# 08_FPGA_banks_1_2_3_4.net
KiCad netlist of a schematic drawn in Altium Designer
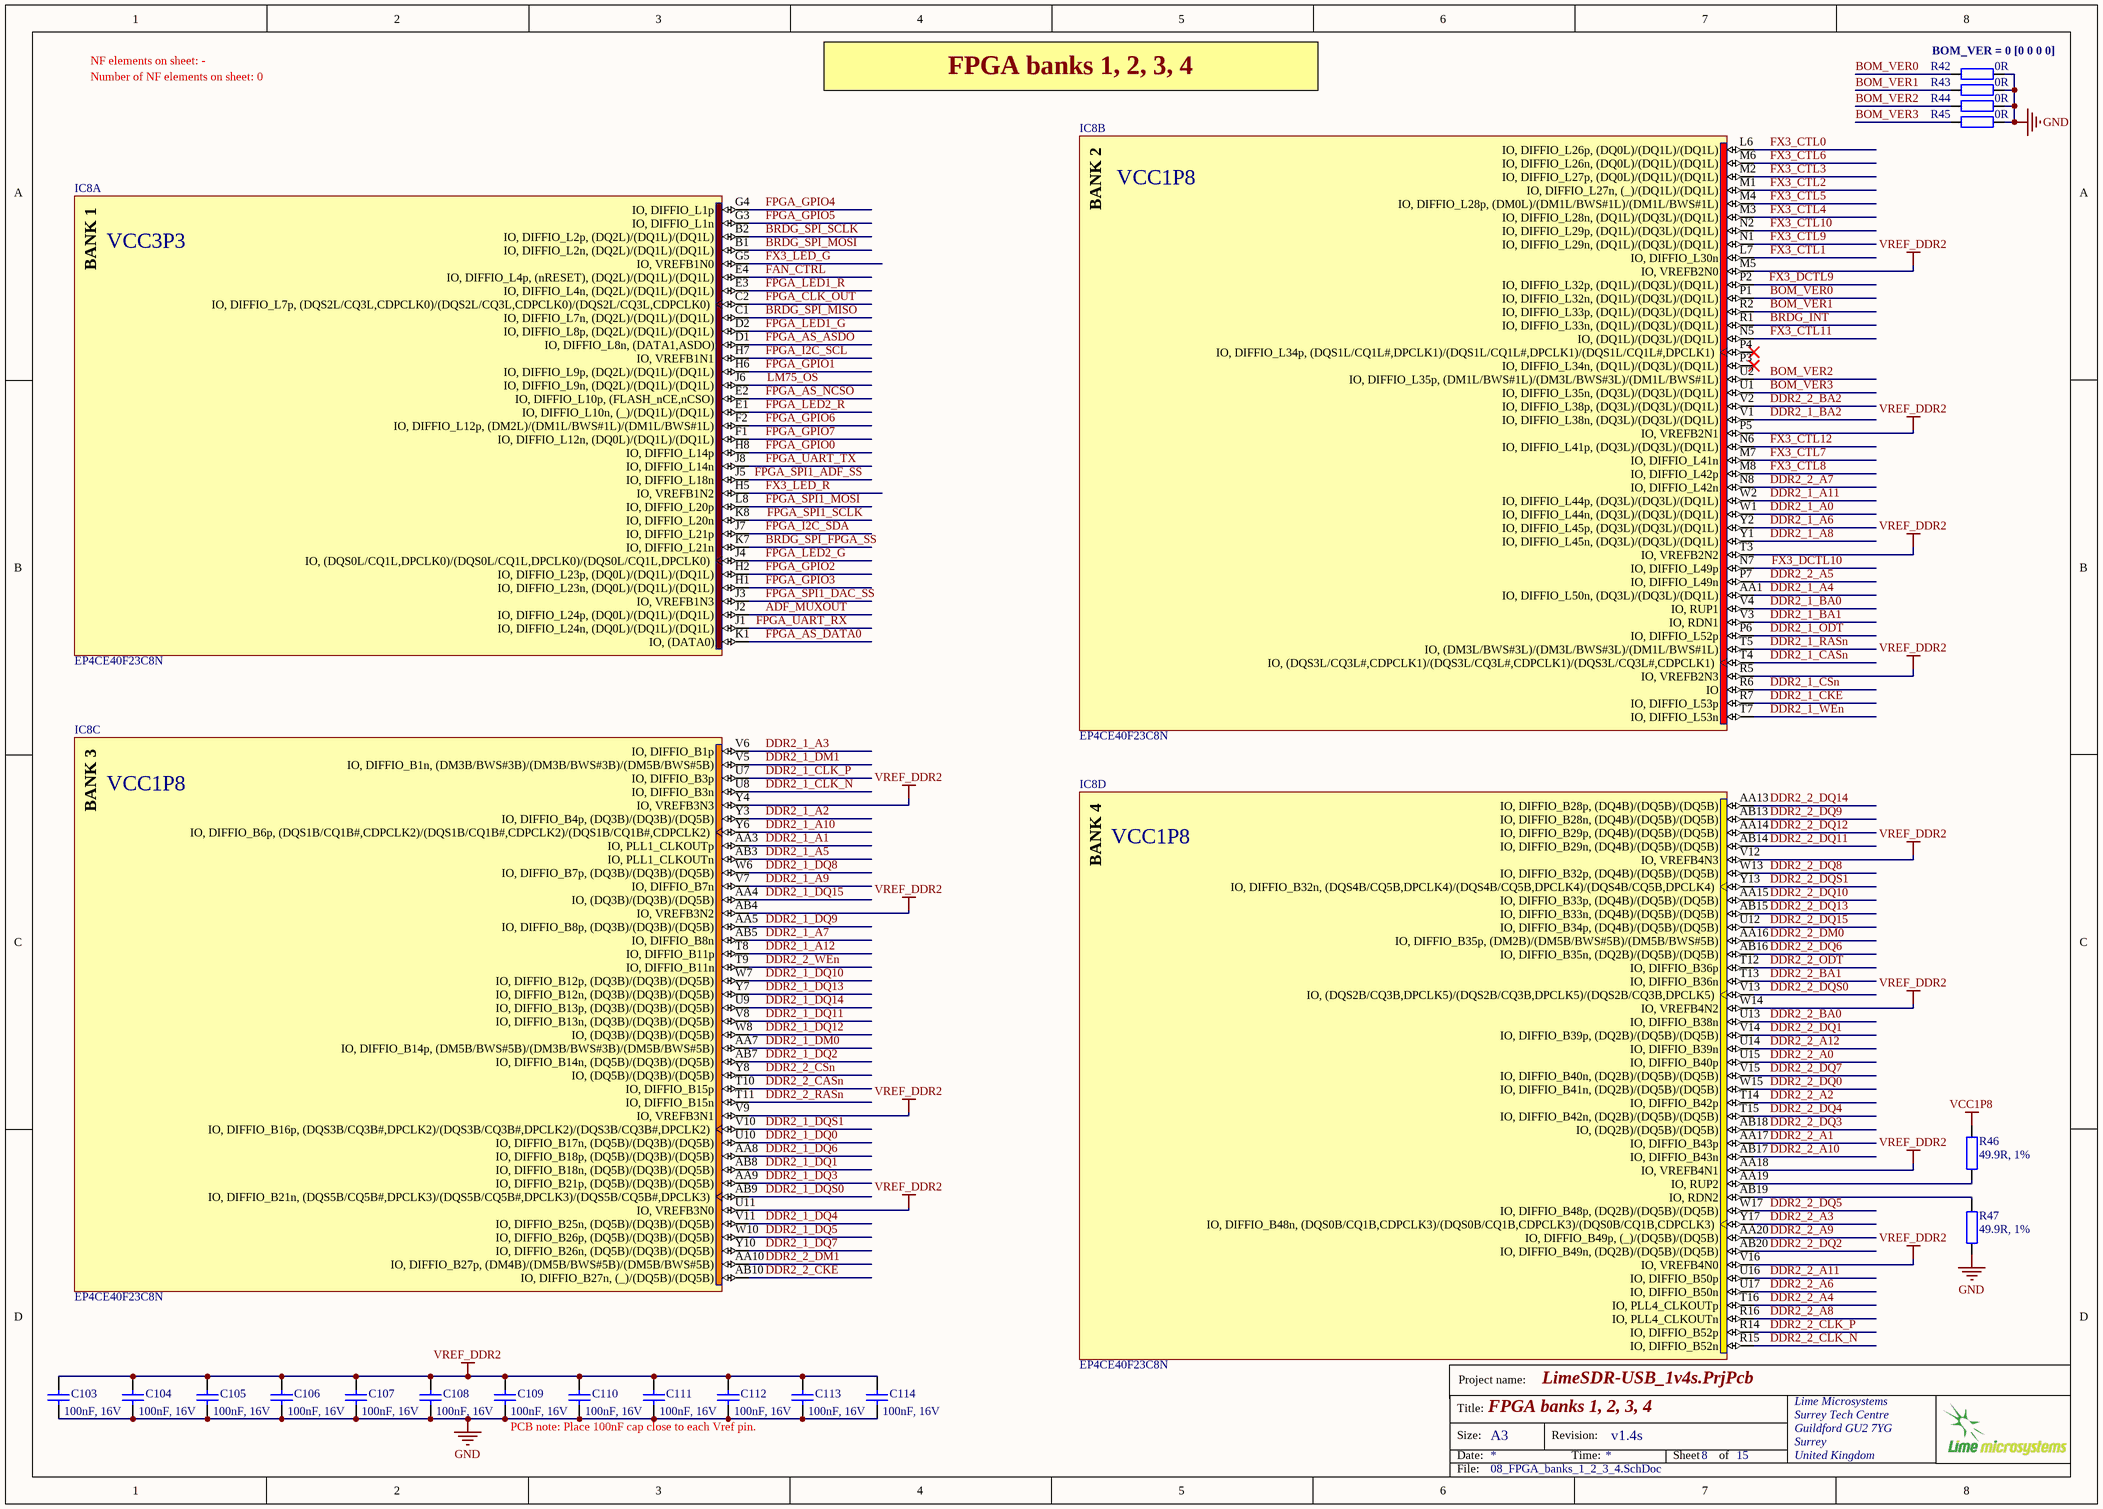
[diagram p0: 08_FPGA_banks_1_2_3_4.SchDoc]

(export (version "E")
  (design (tool "Eeschema 10.0.6"))
  (components
    (comp (ref "C103")
      (value "100nF, 16V")
      (footprint "CAP0402")
      (fields
        (field (name "TOLERANCE") "10 %")
        (field (name "MANUFACTURER") "Murata Electronics")
        (field (name "MANUFACTURER PART NUMBER") "GRM155R71C104KA88D")
      )
      (libsource (lib "LimeFPGAboard_schLib") (part "Cap_0603"))
    )
    (comp (ref "C104")
      (value "100nF, 16V")
      (footprint "CAP0402")
      (fields
        (field (name "TOLERANCE") "10 %")
        (field (name "MANUFACTURER") "Murata Electronics")
        (field (name "MANUFACTURER PART NUMBER") "GRM155R71C104KA88D")
      )
      (libsource (lib "LimeFPGAboard_schLib") (part "Cap_0603"))
    )
    (comp (ref "C105")
      (value "100nF, 16V")
      (footprint "CAP0402")
      (fields
        (field (name "TOLERANCE") "10 %")
        (field (name "MANUFACTURER") "Murata Electronics")
        (field (name "MANUFACTURER PART NUMBER") "GRM155R71C104KA88D")
      )
      (libsource (lib "LimeFPGAboard_schLib") (part "Cap_0603"))
    )
    (comp (ref "C106")
      (value "100nF, 16V")
      (footprint "CAP0402")
      (fields
        (field (name "TOLERANCE") "10 %")
        (field (name "MANUFACTURER") "Murata Electronics")
        (field (name "MANUFACTURER PART NUMBER") "GRM155R71C104KA88D")
      )
      (libsource (lib "LimeFPGAboard_schLib") (part "Cap_0603"))
    )
    (comp (ref "C107")
      (value "100nF, 16V")
      (footprint "CAP0402")
      (fields
        (field (name "TOLERANCE") "10 %")
        (field (name "MANUFACTURER") "Murata Electronics")
        (field (name "MANUFACTURER PART NUMBER") "GRM155R71C104KA88D")
      )
      (libsource (lib "LimeFPGAboard_schLib") (part "Cap_0603"))
    )
    (comp (ref "C108")
      (value "100nF, 16V")
      (footprint "CAP0402")
      (fields
        (field (name "TOLERANCE") "10 %")
        (field (name "MANUFACTURER") "Murata Electronics")
        (field (name "MANUFACTURER PART NUMBER") "GRM155R71C104KA88D")
      )
      (libsource (lib "LimeFPGAboard_schLib") (part "Cap_0603"))
    )
    (comp (ref "C109")
      (value "100nF, 16V")
      (footprint "CAP0402")
      (fields
        (field (name "TOLERANCE") "10 %")
        (field (name "MANUFACTURER") "Murata Electronics")
        (field (name "MANUFACTURER PART NUMBER") "GRM155R71C104KA88D")
      )
      (libsource (lib "LimeFPGAboard_schLib") (part "Cap_0603"))
    )
    (comp (ref "C110")
      (value "100nF, 16V")
      (footprint "CAP0402")
      (fields
        (field (name "TOLERANCE") "10 %")
        (field (name "MANUFACTURER") "Murata Electronics")
        (field (name "MANUFACTURER PART NUMBER") "GRM155R71C104KA88D")
      )
      (libsource (lib "LimeFPGAboard_schLib") (part "Cap_0603"))
    )
    (comp (ref "C111")
      (value "100nF, 16V")
      (footprint "CAP0402")
      (fields
        (field (name "TOLERANCE") "10 %")
        (field (name "MANUFACTURER") "Murata Electronics")
        (field (name "MANUFACTURER PART NUMBER") "GRM155R71C104KA88D")
      )
      (libsource (lib "LimeFPGAboard_schLib") (part "Cap_0603"))
    )
    (comp (ref "C112")
      (value "100nF, 16V")
      (footprint "CAP0402")
      (fields
        (field (name "TOLERANCE") "10 %")
        (field (name "MANUFACTURER") "Murata Electronics")
        (field (name "MANUFACTURER PART NUMBER") "GRM155R71C104KA88D")
      )
      (libsource (lib "LimeFPGAboard_schLib") (part "Cap_0603"))
    )
    (comp (ref "C113")
      (value "100nF, 16V")
      (footprint "CAP0402")
      (fields
        (field (name "TOLERANCE") "10 %")
        (field (name "MANUFACTURER") "Murata Electronics")
        (field (name "MANUFACTURER PART NUMBER") "GRM155R71C104KA88D")
      )
      (libsource (lib "LimeFPGAboard_schLib") (part "Cap_0603"))
    )
    (comp (ref "C114")
      (value "100nF, 16V")
      (footprint "CAP0402")
      (fields
        (field (name "TOLERANCE") "10 %")
        (field (name "MANUFACTURER") "Murata Electronics")
        (field (name "MANUFACTURER PART NUMBER") "GRM155R71C104KA88D")
      )
      (libsource (lib "LimeFPGAboard_schLib") (part "Cap_0603"))
    )
    (comp (ref "IC8")
      (value "EP4CE40F23C8N")
      (footprint "FBGA484_A-240")
      (description "IC FPGA 328 I/O 484FBGA")
      (fields (field (name "MANUFACTURER") "Altera"))
      (libsource (lib "LimeMicroAltiumLib_schLib") (part "EP4CE40F23C7N"))
    )
    (comp (ref "R42")
      (value "0R")
      (footprint "RES0402")
      (fields (field (name "MANUFACTURER") "Yageo"))
      (libsource (lib "LimeFPGAboard_schLib") (part "Res_0402"))
    )
    (comp (ref "R43")
      (value "0R")
      (footprint "RES0402")
      (fields (field (name "MANUFACTURER") "Yageo"))
      (libsource (lib "LimeFPGAboard_schLib") (part "Res_0402"))
    )
    (comp (ref "R44")
      (value "0R")
      (footprint "RES0402")
      (fields (field (name "MANUFACTURER") "Yageo"))
      (libsource (lib "LimeFPGAboard_schLib") (part "Res_0402"))
    )
    (comp (ref "R45")
      (value "0R")
      (footprint "RES0402")
      (fields (field (name "MANUFACTURER") "Yageo"))
      (libsource (lib "LimeFPGAboard_schLib") (part "Res_0402"))
    )
    (comp (ref "R46")
      (value "49.9R, 1%")
      (footprint "RES0402")
      (fields
        (field (name "TOLERANCE") "±1%")
        (field (name "MANUFACTURER") "Samsung Electro-Mechanics America, Inc.")
        (field (name "MANUFACTURER PART NUMBER") "RC1005F49R9CS")
      )
      (libsource (lib "LimeMicroAltiumLib_schLib") (part "Res_0402"))
    )
    (comp (ref "R47")
      (value "49.9R, 1%")
      (footprint "RES0402")
      (fields
        (field (name "TOLERANCE") "±1%")
        (field (name "MANUFACTURER") "Samsung Electro-Mechanics America, Inc.")
        (field (name "MANUFACTURER PART NUMBER") "RC1005F49R9CS")
      )
      (libsource (lib "LimeMicroAltiumLib_schLib") (part "Res_0402"))
    )
  )
  (nets
    (net (code "1") (name "/ADF_MUXOUT") (class "Default")
      (node (ref "IC8") (pin "J2") (pinfunction "IO,_DIFFIO_L24p,_(DQ0L)/(DQ1L)/(DQ1L)_J2") (pintype "bidirectional"))
    )
    (net (code "2") (name "/BOM_VER0") (class "Default")
      (node (ref "IC8") (pin "P1") (pinfunction "IO,_DIFFIO_L32n,_(DQ1L)/(DQ3L)/(DQ1L)_P1") (pintype "bidirectional"))
      (node (ref "R42") (pin "1") (pinfunction "1_1") (pintype "passive"))
    )
    (net (code "3") (name "/BOM_VER1") (class "Default")
      (node (ref "IC8") (pin "R2") (pinfunction "IO,_DIFFIO_L33p,_(DQ1L)/(DQ3L)/(DQ1L)_R2") (pintype "bidirectional"))
      (node (ref "R43") (pin "1") (pinfunction "1_1") (pintype "passive"))
    )
    (net (code "4") (name "/BOM_VER2") (class "Default")
      (node (ref "IC8") (pin "U2") (pinfunction "IO,_DIFFIO_L35p,_(DM1L/BWS#1L)/(DM3L/BWS#3L)/(DM1L/BWS#1L)_U2") (pintype "bidirectional"))
      (node (ref "R44") (pin "1") (pinfunction "1_1") (pintype "passive"))
    )
    (net (code "5") (name "/BOM_VER3") (class "Default")
      (node (ref "IC8") (pin "U1") (pinfunction "IO,_DIFFIO_L35n,_(DQ3L)/(DQ3L)/(DQ1L)_U1") (pintype "bidirectional"))
      (node (ref "R45") (pin "1") (pinfunction "1_1") (pintype "passive"))
    )
    (net (code "6") (name "/BRDG_INT") (class "Default")
      (node (ref "IC8") (pin "R1") (pinfunction "IO,_DIFFIO_L33n,_(DQ1L)/(DQ3L)/(DQ1L)_R1") (pintype "bidirectional"))
    )
    (net (code "7") (name "/BRDG_SPI_FPGA_SS") (class "Default")
      (node (ref "IC8") (pin "K7") (pinfunction "IO,_DIFFIO_L21n_K7") (pintype "bidirectional"))
    )
    (net (code "8") (name "/BRDG_SPI_MISO") (class "Default")
      (node (ref "IC8") (pin "C1") (pinfunction "IO,_DIFFIO_L7n,_(DQ2L)/(DQ1L)/(DQ1L)_C1") (pintype "bidirectional"))
    )
    (net (code "9") (name "/BRDG_SPI_MOSI") (class "Default")
      (node (ref "IC8") (pin "B1") (pinfunction "IO,_DIFFIO_L2n,_(DQ2L)/(DQ1L)/(DQ1L)_B1") (pintype "bidirectional"))
    )
    (net (code "10") (name "/BRDG_SPI_SCLK") (class "Default")
      (node (ref "IC8") (pin "B2") (pinfunction "IO,_DIFFIO_L2p,_(DQ2L)/(DQ1L)/(DQ1L)_B2") (pintype "bidirectional"))
    )
    (net (code "11") (name "/DDR2_1_A0") (class "Default")
      (node (ref "IC8") (pin "W1") (pinfunction "IO,_DIFFIO_L44n,_(DQ3L)/(DQ3L)/(DQ1L)_W1") (pintype "bidirectional"))
    )
    (net (code "12") (name "/DDR2_1_A1") (class "Default")
      (node (ref "IC8") (pin "AA3") (pinfunction "IO,_PLL1_CLKOUTp_AA3") (pintype "bidirectional"))
    )
    (net (code "13") (name "/DDR2_1_A2") (class "Default")
      (node (ref "IC8") (pin "Y3") (pinfunction "IO,_DIFFIO_B4p,_(DQ3B)/(DQ3B)/(DQ5B)_Y3") (pintype "bidirectional"))
    )
    (net (code "14") (name "/DDR2_1_A3") (class "Default")
      (node (ref "IC8") (pin "V6") (pinfunction "IO,_DIFFIO_B1p_V6") (pintype "bidirectional"))
    )
    (net (code "15") (name "/DDR2_1_A4") (class "Default")
      (node (ref "IC8") (pin "AA1") (pinfunction "IO,_DIFFIO_L50n,_(DQ3L)/(DQ3L)/(DQ1L)_AA1") (pintype "bidirectional"))
    )
    (net (code "16") (name "/DDR2_1_A5") (class "Default")
      (node (ref "IC8") (pin "AB3") (pinfunction "IO,_PLL1_CLKOUTn_AB3") (pintype "bidirectional"))
    )
    (net (code "17") (name "/DDR2_1_A6") (class "Default")
      (node (ref "IC8") (pin "Y2") (pinfunction "IO,_DIFFIO_L45p,_(DQ3L)/(DQ3L)/(DQ1L)_Y2") (pintype "bidirectional"))
    )
    (net (code "18") (name "/DDR2_1_A7") (class "Default")
      (node (ref "IC8") (pin "AB5") (pinfunction "IO,_DIFFIO_B8n_AB5") (pintype "bidirectional"))
    )
    (net (code "19") (name "/DDR2_1_A8") (class "Default")
      (node (ref "IC8") (pin "Y1") (pinfunction "IO,_DIFFIO_L45n,_(DQ3L)/(DQ3L)/(DQ1L)_Y1") (pintype "bidirectional"))
    )
    (net (code "20") (name "/DDR2_1_A9") (class "Default")
      (node (ref "IC8") (pin "V7") (pinfunction "IO,_DIFFIO_B7n_V7") (pintype "bidirectional"))
    )
    (net (code "21") (name "/DDR2_1_A10") (class "Default")
      (node (ref "IC8") (pin "Y6") (pinfunction "IO,_DIFFIO_B6p,_(DQS1B/CQ1B#,CDPCLK2)/(DQS1B/CQ1B#,CDPCLK2)/(DQS1B/CQ1B#,CDPCLK2)_Y6") (pintype "bidirectional"))
    )
    (net (code "22") (name "/DDR2_1_A11") (class "Default")
      (node (ref "IC8") (pin "W2") (pinfunction "IO,_DIFFIO_L44p,_(DQ3L)/(DQ3L)/(DQ1L)_W2") (pintype "bidirectional"))
    )
    (net (code "23") (name "/DDR2_1_A12") (class "Default")
      (node (ref "IC8") (pin "T8") (pinfunction "IO,_DIFFIO_B11p_T8") (pintype "bidirectional"))
    )
    (net (code "24") (name "/DDR2_1_BA0") (class "Default")
      (node (ref "IC8") (pin "V4") (pinfunction "IO,_RUP1_V4") (pintype "bidirectional"))
    )
    (net (code "25") (name "/DDR2_1_BA1") (class "Default")
      (node (ref "IC8") (pin "V3") (pinfunction "IO,_RDN1_V3") (pintype "bidirectional"))
    )
    (net (code "26") (name "/DDR2_1_BA2") (class "Default")
      (node (ref "IC8") (pin "V1") (pinfunction "IO,_DIFFIO_L38n,_(DQ3L)/(DQ3L)/(DQ1L)_V1") (pintype "bidirectional"))
    )
    (net (code "27") (name "/DDR2_1_CASn") (class "Default")
      (node (ref "IC8") (pin "T4") (pinfunction "IO,_(DQS3L/CQ3L#,CDPCLK1)/(DQS3L/CQ3L#,CDPCLK1)/(DQS3L/CQ3L#,CDPCLK1)_T4") (pintype "bidirectional"))
    )
    (net (code "28") (name "/DDR2_1_CKE") (class "Default")
      (node (ref "IC8") (pin "R7") (pinfunction "IO,_DIFFIO_L53p_R7") (pintype "bidirectional"))
    )
    (net (code "29") (name "/DDR2_1_CLK_N") (class "Default")
      (node (ref "IC8") (pin "U8") (pinfunction "IO,_DIFFIO_B3n_U8") (pintype "bidirectional"))
    )
    (net (code "30") (name "/DDR2_1_CLK_P") (class "Default")
      (node (ref "IC8") (pin "U7") (pinfunction "IO,_DIFFIO_B3p_U7") (pintype "bidirectional"))
    )
    (net (code "31") (name "/DDR2_1_CSn") (class "Default")
      (node (ref "IC8") (pin "R6") (pinfunction "IO_R6") (pintype "bidirectional"))
    )
    (net (code "32") (name "/DDR2_1_DM0") (class "Default")
      (node (ref "IC8") (pin "AA7") (pinfunction "IO,_DIFFIO_B14p,_(DM5B/BWS#5B)/(DM3B/BWS#3B)/(DM5B/BWS#5B)_AA7") (pintype "bidirectional"))
    )
    (net (code "33") (name "/DDR2_1_DM1") (class "Default")
      (node (ref "IC8") (pin "V5") (pinfunction "IO,_DIFFIO_B1n,_(DM3B/BWS#3B)/(DM3B/BWS#3B)/(DM5B/BWS#5B)_V5") (pintype "bidirectional"))
    )
    (net (code "34") (name "/DDR2_1_DQ0") (class "Default")
      (node (ref "IC8") (pin "U10") (pinfunction "IO,_DIFFIO_B17n,_(DQ5B)/(DQ3B)/(DQ5B)_U10") (pintype "bidirectional"))
    )
    (net (code "35") (name "/DDR2_1_DQ1") (class "Default")
      (node (ref "IC8") (pin "AB8") (pinfunction "IO,_DIFFIO_B18n,_(DQ5B)/(DQ3B)/(DQ5B)_AB8") (pintype "bidirectional"))
    )
    (net (code "36") (name "/DDR2_1_DQ2") (class "Default")
      (node (ref "IC8") (pin "AB7") (pinfunction "IO,_DIFFIO_B14n,_(DQ5B)/(DQ3B)/(DQ5B)_AB7") (pintype "bidirectional"))
    )
    (net (code "37") (name "/DDR2_1_DQ3") (class "Default")
      (node (ref "IC8") (pin "AA9") (pinfunction "IO,_DIFFIO_B21p,_(DQ5B)/(DQ3B)/(DQ5B)_AA9") (pintype "bidirectional"))
    )
    (net (code "38") (name "/DDR2_1_DQ4") (class "Default")
      (node (ref "IC8") (pin "V11") (pinfunction "IO,_DIFFIO_B25n,_(DQ5B)/(DQ3B)/(DQ5B)_V11") (pintype "bidirectional"))
    )
    (net (code "39") (name "/DDR2_1_DQ5") (class "Default")
      (node (ref "IC8") (pin "W10") (pinfunction "IO,_DIFFIO_B26p,_(DQ5B)/(DQ3B)/(DQ5B)_W10") (pintype "bidirectional"))
    )
    (net (code "40") (name "/DDR2_1_DQ6") (class "Default")
      (node (ref "IC8") (pin "AA8") (pinfunction "IO,_DIFFIO_B18p,_(DQ5B)/(DQ3B)/(DQ5B)_AA8") (pintype "bidirectional"))
    )
    (net (code "41") (name "/DDR2_1_DQ7") (class "Default")
      (node (ref "IC8") (pin "Y10") (pinfunction "IO,_DIFFIO_B26n,_(DQ5B)/(DQ3B)/(DQ5B)_Y10") (pintype "bidirectional"))
    )
    (net (code "42") (name "/DDR2_1_DQ8") (class "Default")
      (node (ref "IC8") (pin "W6") (pinfunction "IO,_DIFFIO_B7p,_(DQ3B)/(DQ3B)/(DQ5B)_W6") (pintype "bidirectional"))
    )
    (net (code "43") (name "/DDR2_1_DQ9") (class "Default")
      (node (ref "IC8") (pin "AA5") (pinfunction "IO,_DIFFIO_B8p,_(DQ3B)/(DQ3B)/(DQ5B)_AA5") (pintype "bidirectional"))
    )
    (net (code "44") (name "/DDR2_1_DQ10") (class "Default")
      (node (ref "IC8") (pin "W7") (pinfunction "IO,_DIFFIO_B12p,_(DQ3B)/(DQ3B)/(DQ5B)_W7") (pintype "bidirectional"))
    )
    (net (code "45") (name "/DDR2_1_DQ11") (class "Default")
      (node (ref "IC8") (pin "V8") (pinfunction "IO,_DIFFIO_B13n,_(DQ3B)/(DQ3B)/(DQ5B)_V8") (pintype "bidirectional"))
    )
    (net (code "46") (name "/DDR2_1_DQ12") (class "Default")
      (node (ref "IC8") (pin "W8") (pinfunction "IO,_(DQ3B)/(DQ3B)/(DQ5B)_W8") (pintype "bidirectional"))
    )
    (net (code "47") (name "/DDR2_1_DQ13") (class "Default")
      (node (ref "IC8") (pin "Y7") (pinfunction "IO,_DIFFIO_B12n,_(DQ3B)/(DQ3B)/(DQ5B)_Y7") (pintype "bidirectional"))
    )
    (net (code "48") (name "/DDR2_1_DQ14") (class "Default")
      (node (ref "IC8") (pin "U9") (pinfunction "IO,_DIFFIO_B13p,_(DQ3B)/(DQ3B)/(DQ5B)_U9") (pintype "bidirectional"))
    )
    (net (code "49") (name "/DDR2_1_DQ15") (class "Default")
      (node (ref "IC8") (pin "AA4") (pinfunction "IO,_(DQ3B)/(DQ3B)/(DQ5B)_AA4") (pintype "bidirectional"))
    )
    (net (code "50") (name "/DDR2_1_DQS0") (class "Default")
      (node (ref "IC8") (pin "AB9") (pinfunction "IO,_DIFFIO_B21n,_(DQS5B/CQ5B#,DPCLK3)/(DQS5B/CQ5B#,DPCLK3)/(DQS5B/CQ5B#,DPCLK3)_AB9") (pintype "bidirectional"))
    )
    (net (code "51") (name "/DDR2_1_DQS1") (class "Default")
      (node (ref "IC8") (pin "V10") (pinfunction "IO,_DIFFIO_B16p,_(DQS3B/CQ3B#,DPCLK2)/(DQS3B/CQ3B#,DPCLK2)/(DQS3B/CQ3B#,DPCLK2)_V10") (pintype "bidirectional"))
    )
    (net (code "52") (name "/DDR2_1_ODT") (class "Default")
      (node (ref "IC8") (pin "P6") (pinfunction "IO,_DIFFIO_L52p_P6") (pintype "bidirectional"))
    )
    (net (code "53") (name "/DDR2_1_RASn") (class "Default")
      (node (ref "IC8") (pin "T5") (pinfunction "IO,_(DM3L/BWS#3L)/(DM3L/BWS#3L)/(DM1L/BWS#1L)_T5") (pintype "bidirectional"))
    )
    (net (code "54") (name "/DDR2_1_WEn") (class "Default")
      (node (ref "IC8") (pin "T7") (pinfunction "IO,_DIFFIO_L53n_T7") (pintype "bidirectional"))
    )
    (net (code "55") (name "/DDR2_2_A0") (class "Default")
      (node (ref "IC8") (pin "U15") (pinfunction "IO,_DIFFIO_B40p_U15") (pintype "bidirectional"))
    )
    (net (code "56") (name "/DDR2_2_A1") (class "Default")
      (node (ref "IC8") (pin "AA17") (pinfunction "IO,_DIFFIO_B43p_AA17") (pintype "bidirectional"))
    )
    (net (code "57") (name "/DDR2_2_A2") (class "Default")
      (node (ref "IC8") (pin "T14") (pinfunction "IO,_DIFFIO_B42p_T14") (pintype "bidirectional"))
    )
    (net (code "58") (name "/DDR2_2_A3") (class "Default")
      (node (ref "IC8") (pin "Y17") (pinfunction "IO,_DIFFIO_B48n,_(DQS0B/CQ1B,CDPCLK3)/(DQS0B/CQ1B,CDPCLK3)/(DQS0B/CQ1B,CDPCLK3)_Y17") (pintype "bidirectional"))
    )
    (net (code "59") (name "/DDR2_2_A4") (class "Default")
      (node (ref "IC8") (pin "T16") (pinfunction "IO,_PLL4_CLKOUTp_T16") (pintype "bidirectional"))
    )
    (net (code "60") (name "/DDR2_2_A5") (class "Default")
      (node (ref "IC8") (pin "P7") (pinfunction "IO,_DIFFIO_L49n_P7") (pintype "bidirectional"))
    )
    (net (code "61") (name "/DDR2_2_A6") (class "Default")
      (node (ref "IC8") (pin "U17") (pinfunction "IO,_DIFFIO_B50n_U17") (pintype "bidirectional"))
    )
    (net (code "62") (name "/DDR2_2_A7") (class "Default")
      (node (ref "IC8") (pin "N8") (pinfunction "IO,_DIFFIO_L42n_N8") (pintype "bidirectional"))
    )
    (net (code "63") (name "/DDR2_2_A8") (class "Default")
      (node (ref "IC8") (pin "R16") (pinfunction "IO,_PLL4_CLKOUTn_R16") (pintype "bidirectional"))
    )
    (net (code "64") (name "/DDR2_2_A9") (class "Default")
      (node (ref "IC8") (pin "AA20") (pinfunction "IO,_DIFFIO_B49p,_(_)/(DQ5B)/(DQ5B)_AA20") (pintype "bidirectional"))
    )
    (net (code "65") (name "/DDR2_2_A10") (class "Default")
      (node (ref "IC8") (pin "AB17") (pinfunction "IO,_DIFFIO_B43n_AB17") (pintype "bidirectional"))
    )
    (net (code "66") (name "/DDR2_2_A11") (class "Default")
      (node (ref "IC8") (pin "U16") (pinfunction "IO,_DIFFIO_B50p_U16") (pintype "bidirectional"))
    )
    (net (code "67") (name "/DDR2_2_A12") (class "Default")
      (node (ref "IC8") (pin "U14") (pinfunction "IO,_DIFFIO_B39n_U14") (pintype "bidirectional"))
    )
    (net (code "68") (name "/DDR2_2_BA0") (class "Default")
      (node (ref "IC8") (pin "U13") (pinfunction "IO,_DIFFIO_B38n_U13") (pintype "bidirectional"))
    )
    (net (code "69") (name "/DDR2_2_BA1") (class "Default")
      (node (ref "IC8") (pin "T13") (pinfunction "IO,_DIFFIO_B36n_T13") (pintype "bidirectional"))
    )
    (net (code "70") (name "/DDR2_2_BA2") (class "Default")
      (node (ref "IC8") (pin "V2") (pinfunction "IO,_DIFFIO_L38p,_(DQ3L)/(DQ3L)/(DQ1L)_V2") (pintype "bidirectional"))
    )
    (net (code "71") (name "/DDR2_2_CASn") (class "Default")
      (node (ref "IC8") (pin "T10") (pinfunction "IO,_DIFFIO_B15p_T10") (pintype "bidirectional"))
    )
    (net (code "72") (name "/DDR2_2_CKE") (class "Default")
      (node (ref "IC8") (pin "AB10") (pinfunction "IO,_DIFFIO_B27n,_(_)/(DQ5B)/(DQ5B)_AB10") (pintype "bidirectional"))
    )
    (net (code "73") (name "/DDR2_2_CLK_N") (class "Default")
      (node (ref "IC8") (pin "R15") (pinfunction "IO,_DIFFIO_B52n_R15") (pintype "bidirectional"))
    )
    (net (code "74") (name "/DDR2_2_CLK_P") (class "Default")
      (node (ref "IC8") (pin "R14") (pinfunction "IO,_DIFFIO_B52p_R14") (pintype "bidirectional"))
    )
    (net (code "75") (name "/DDR2_2_CSn") (class "Default")
      (node (ref "IC8") (pin "Y8") (pinfunction "IO,_(DQ5B)/(DQ3B)/(DQ5B)_Y8") (pintype "bidirectional"))
    )
    (net (code "76") (name "/DDR2_2_DM0") (class "Default")
      (node (ref "IC8") (pin "AA16") (pinfunction "IO,_DIFFIO_B35p,_(DM2B)/(DM5B/BWS#5B)/(DM5B/BWS#5B)_AA16") (pintype "bidirectional"))
    )
    (net (code "77") (name "/DDR2_2_DM1") (class "Default")
      (node (ref "IC8") (pin "AA10") (pinfunction "IO,_DIFFIO_B27p,_(DM4B)/(DM5B/BWS#5B)/(DM5B/BWS#5B)_AA10") (pintype "bidirectional"))
    )
    (net (code "78") (name "/DDR2_2_DQ0") (class "Default")
      (node (ref "IC8") (pin "W15") (pinfunction "IO,_DIFFIO_B41n,_(DQ2B)/(DQ5B)/(DQ5B)_W15") (pintype "bidirectional"))
    )
    (net (code "79") (name "/DDR2_2_DQ1") (class "Default")
      (node (ref "IC8") (pin "V14") (pinfunction "IO,_DIFFIO_B39p,_(DQ2B)/(DQ5B)/(DQ5B)_V14") (pintype "bidirectional"))
    )
    (net (code "80") (name "/DDR2_2_DQ2") (class "Default")
      (node (ref "IC8") (pin "AB20") (pinfunction "IO,_DIFFIO_B49n,_(DQ2B)/(DQ5B)/(DQ5B)_AB20") (pintype "bidirectional"))
    )
    (net (code "81") (name "/DDR2_2_DQ3") (class "Default")
      (node (ref "IC8") (pin "AB18") (pinfunction "IO,_(DQ2B)/(DQ5B)/(DQ5B)_AB18") (pintype "bidirectional"))
    )
    (net (code "82") (name "/DDR2_2_DQ4") (class "Default")
      (node (ref "IC8") (pin "T15") (pinfunction "IO,_DIFFIO_B42n,_(DQ2B)/(DQ5B)/(DQ5B)_T15") (pintype "bidirectional"))
    )
    (net (code "83") (name "/DDR2_2_DQ5") (class "Default")
      (node (ref "IC8") (pin "W17") (pinfunction "IO,_DIFFIO_B48p,_(DQ2B)/(DQ5B)/(DQ5B)_W17") (pintype "bidirectional"))
    )
    (net (code "84") (name "/DDR2_2_DQ6") (class "Default")
      (node (ref "IC8") (pin "AB16") (pinfunction "IO,_DIFFIO_B35n,_(DQ2B)/(DQ5B)/(DQ5B)_AB16") (pintype "bidirectional"))
    )
    (net (code "85") (name "/DDR2_2_DQ7") (class "Default")
      (node (ref "IC8") (pin "V15") (pinfunction "IO,_DIFFIO_B40n,_(DQ2B)/(DQ5B)/(DQ5B)_V15") (pintype "bidirectional"))
    )
    (net (code "86") (name "/DDR2_2_DQ8") (class "Default")
      (node (ref "IC8") (pin "W13") (pinfunction "IO,_DIFFIO_B32p,_(DQ4B)/(DQ5B)/(DQ5B)_W13") (pintype "bidirectional"))
    )
    (net (code "87") (name "/DDR2_2_DQ9") (class "Default")
      (node (ref "IC8") (pin "AB13") (pinfunction "IO,_DIFFIO_B28n,_(DQ4B)/(DQ5B)/(DQ5B)_AB13") (pintype "bidirectional"))
    )
    (net (code "88") (name "/DDR2_2_DQ10") (class "Default")
      (node (ref "IC8") (pin "AA15") (pinfunction "IO,_DIFFIO_B33p,_(DQ4B)/(DQ5B)/(DQ5B)_AA15") (pintype "bidirectional"))
    )
    (net (code "89") (name "/DDR2_2_DQ11") (class "Default")
      (node (ref "IC8") (pin "AB14") (pinfunction "IO,_DIFFIO_B29n,_(DQ4B)/(DQ5B)/(DQ5B)_AB14") (pintype "bidirectional"))
    )
    (net (code "90") (name "/DDR2_2_DQ12") (class "Default")
      (node (ref "IC8") (pin "AA14") (pinfunction "IO,_DIFFIO_B29p,_(DQ4B)/(DQ5B)/(DQ5B)_AA14") (pintype "bidirectional"))
    )
    (net (code "91") (name "/DDR2_2_DQ13") (class "Default")
      (node (ref "IC8") (pin "AB15") (pinfunction "IO,_DIFFIO_B33n,_(DQ4B)/(DQ5B)/(DQ5B)_AB15") (pintype "bidirectional"))
    )
    (net (code "92") (name "/DDR2_2_DQ14") (class "Default")
      (node (ref "IC8") (pin "AA13") (pinfunction "IO,_DIFFIO_B28p,_(DQ4B)/(DQ5B)/(DQ5B)_AA13") (pintype "bidirectional"))
    )
    (net (code "93") (name "/DDR2_2_DQ15") (class "Default")
      (node (ref "IC8") (pin "U12") (pinfunction "IO,_DIFFIO_B34p,_(DQ4B)/(DQ5B)/(DQ5B)_U12") (pintype "bidirectional"))
    )
    (net (code "94") (name "/DDR2_2_DQS0") (class "Default")
      (node (ref "IC8") (pin "V13") (pinfunction "IO,_(DQS2B/CQ3B,DPCLK5)/(DQS2B/CQ3B,DPCLK5)/(DQS2B/CQ3B,DPCLK5)_V13") (pintype "bidirectional"))
    )
    (net (code "95") (name "/DDR2_2_DQS1") (class "Default")
      (node (ref "IC8") (pin "Y13") (pinfunction "IO,_DIFFIO_B32n,_(DQS4B/CQ5B,DPCLK4)/(DQS4B/CQ5B,DPCLK4)/(DQS4B/CQ5B,DPCLK4)_Y13") (pintype "bidirectional"))
    )
    (net (code "96") (name "/DDR2_2_ODT") (class "Default")
      (node (ref "IC8") (pin "T12") (pinfunction "IO,_DIFFIO_B36p_T12") (pintype "bidirectional"))
    )
    (net (code "97") (name "/DDR2_2_RASn") (class "Default")
      (node (ref "IC8") (pin "T11") (pinfunction "IO,_DIFFIO_B15n_T11") (pintype "bidirectional"))
    )
    (net (code "98") (name "/DDR2_2_WEn") (class "Default")
      (node (ref "IC8") (pin "T9") (pinfunction "IO,_DIFFIO_B11n_T9") (pintype "bidirectional"))
    )
    (net (code "99") (name "/FAN_CTRL") (class "Default")
      (node (ref "IC8") (pin "E4") (pinfunction "IO,_DIFFIO_L4p,_(nRESET),_(DQ2L)/(DQ1L)/(DQ1L)_E4") (pintype "bidirectional"))
    )
    (net (code "100") (name "/FPGA_AS_ASDO") (class "Default")
      (node (ref "IC8") (pin "D1") (pinfunction "IO,_DIFFIO_L8n,_(DATA1,ASDO)_D1") (pintype "bidirectional"))
    )
    (net (code "101") (name "/FPGA_AS_DATA0") (class "Default")
      (node (ref "IC8") (pin "K1") (pinfunction "IO,_(DATA0)_K1") (pintype "bidirectional"))
    )
    (net (code "102") (name "/FPGA_AS_NCSO") (class "Default")
      (node (ref "IC8") (pin "E2") (pinfunction "IO,_DIFFIO_L10p,_(FLASH_nCE,nCSO)_E2") (pintype "bidirectional"))
    )
    (net (code "103") (name "/FPGA_CLK_OUT") (class "Default")
      (node (ref "IC8") (pin "C2") (pinfunction "IO,_DIFFIO_L7p,_(DQS2L/CQ3L,CDPCLK0)/(DQS2L/CQ3L,CDPCLK0)/(DQS2L/CQ3L,CDPCLK0)_C2") (pintype "bidirectional"))
    )
    (net (code "104") (name "/FPGA_GPIO0") (class "Default")
      (node (ref "IC8") (pin "H8") (pinfunction "IO,_DIFFIO_L14p_H8") (pintype "bidirectional"))
    )
    (net (code "105") (name "/FPGA_GPIO1") (class "Default")
      (node (ref "IC8") (pin "H6") (pinfunction "IO,_DIFFIO_L9p,_(DQ2L)/(DQ1L)/(DQ1L)_H6") (pintype "bidirectional"))
    )
    (net (code "106") (name "/FPGA_GPIO2") (class "Default")
      (node (ref "IC8") (pin "H2") (pinfunction "IO,_DIFFIO_L23p,_(DQ0L)/(DQ1L)/(DQ1L)_H2") (pintype "bidirectional"))
    )
    (net (code "107") (name "/FPGA_GPIO3") (class "Default")
      (node (ref "IC8") (pin "H1") (pinfunction "IO,_DIFFIO_L23n,_(DQ0L)/(DQ1L)/(DQ1L)_H1") (pintype "bidirectional"))
    )
    (net (code "108") (name "/FPGA_GPIO4") (class "Default")
      (node (ref "IC8") (pin "G4") (pinfunction "IO,_DIFFIO_L1p_G4") (pintype "bidirectional"))
    )
    (net (code "109") (name "/FPGA_GPIO5") (class "Default")
      (node (ref "IC8") (pin "G3") (pinfunction "IO,_DIFFIO_L1n_G3") (pintype "bidirectional"))
    )
    (net (code "110") (name "/FPGA_GPIO6") (class "Default")
      (node (ref "IC8") (pin "F2") (pinfunction "IO,_DIFFIO_L12p,_(DM2L)/(DM1L/BWS#1L)/(DM1L/BWS#1L)_F2") (pintype "bidirectional"))
    )
    (net (code "111") (name "/FPGA_GPIO7") (class "Default")
      (node (ref "IC8") (pin "F1") (pinfunction "IO,_DIFFIO_L12n,_(DQ0L)/(DQ1L)/(DQ1L)_F1") (pintype "bidirectional"))
    )
    (net (code "112") (name "/FPGA_I2C_SCL") (class "Default")
      (node (ref "IC8") (pin "H7") (pinfunction "IO,_VREFB1N1_H7") (pintype "bidirectional"))
    )
    (net (code "113") (name "/FPGA_I2C_SDA") (class "Default")
      (node (ref "IC8") (pin "J7") (pinfunction "IO,_DIFFIO_L21p_J7") (pintype "bidirectional"))
    )
    (net (code "114") (name "/FPGA_LED1_G") (class "Default")
      (node (ref "IC8") (pin "D2") (pinfunction "IO,_DIFFIO_L8p,_(DQ2L)/(DQ1L)/(DQ1L)_D2") (pintype "bidirectional"))
    )
    (net (code "115") (name "/FPGA_LED1_R") (class "Default")
      (node (ref "IC8") (pin "E3") (pinfunction "IO,_DIFFIO_L4n,_(DQ2L)/(DQ1L)/(DQ1L)_E3") (pintype "bidirectional"))
    )
    (net (code "116") (name "/FPGA_LED2_G") (class "Default")
      (node (ref "IC8") (pin "J4") (pinfunction "IO,_(DQS0L/CQ1L,DPCLK0)/(DQS0L/CQ1L,DPCLK0)/(DQS0L/CQ1L,DPCLK0)_J4") (pintype "bidirectional"))
    )
    (net (code "117") (name "/FPGA_LED2_R") (class "Default")
      (node (ref "IC8") (pin "E1") (pinfunction "IO,_DIFFIO_L10n,_(_)/(DQ1L)/(DQ1L)_E1") (pintype "bidirectional"))
    )
    (net (code "118") (name "/FPGA_SPI1_ADF_SS") (class "Default")
      (node (ref "IC8") (pin "J5") (pinfunction "IO,_DIFFIO_L18n_J5") (pintype "bidirectional"))
    )
    (net (code "119") (name "/FPGA_SPI1_DAC_SS") (class "Default")
      (node (ref "IC8") (pin "J3") (pinfunction "IO,_VREFB1N3_J3") (pintype "bidirectional"))
    )
    (net (code "120") (name "/FPGA_SPI1_MOSI") (class "Default")
      (node (ref "IC8") (pin "L8") (pinfunction "IO,_DIFFIO_L20p_L8") (pintype "bidirectional"))
    )
    (net (code "121") (name "/FPGA_SPI1_SCLK") (class "Default")
      (node (ref "IC8") (pin "K8") (pinfunction "IO,_DIFFIO_L20n_K8") (pintype "bidirectional"))
    )
    (net (code "122") (name "/FPGA_UART_RX") (class "Default")
      (node (ref "IC8") (pin "J1") (pinfunction "IO,_DIFFIO_L24n,_(DQ0L)/(DQ1L)/(DQ1L)_J1") (pintype "bidirectional"))
    )
    (net (code "123") (name "/FPGA_UART_TX") (class "Default")
      (node (ref "IC8") (pin "J8") (pinfunction "IO,_DIFFIO_L14n_J8") (pintype "bidirectional"))
    )
    (net (code "124") (name "/FX3_CTL0") (class "Default")
      (node (ref "IC8") (pin "L6") (pinfunction "IO,_DIFFIO_L26p,_(DQ0L)/(DQ1L)/(DQ1L)_L6") (pintype "bidirectional"))
    )
    (net (code "125") (name "/FX3_CTL1") (class "Default")
      (node (ref "IC8") (pin "L7") (pinfunction "IO,_DIFFIO_L30n_L7") (pintype "bidirectional"))
    )
    (net (code "126") (name "/FX3_CTL2") (class "Default")
      (node (ref "IC8") (pin "M1") (pinfunction "IO,_DIFFIO_L27n,_(_)/(DQ1L)/(DQ1L)_M1") (pintype "bidirectional"))
    )
    (net (code "127") (name "/FX3_CTL3") (class "Default")
      (node (ref "IC8") (pin "M2") (pinfunction "IO,_DIFFIO_L27p,_(DQ0L)/(DQ1L)/(DQ1L)_M2") (pintype "bidirectional"))
    )
    (net (code "128") (name "/FX3_CTL4") (class "Default")
      (node (ref "IC8") (pin "M3") (pinfunction "IO,_DIFFIO_L28n,_(DQ1L)/(DQ3L)/(DQ1L)_M3") (pintype "bidirectional"))
    )
    (net (code "129") (name "/FX3_CTL5") (class "Default")
      (node (ref "IC8") (pin "M4") (pinfunction "IO,_DIFFIO_L28p,_(DM0L)/(DM1L/BWS#1L)/(DM1L/BWS#1L)_M4") (pintype "bidirectional"))
    )
    (net (code "130") (name "/FX3_CTL6") (class "Default")
      (node (ref "IC8") (pin "M6") (pinfunction "IO,_DIFFIO_L26n,_(DQ0L)/(DQ1L)/(DQ1L)_M6") (pintype "bidirectional"))
    )
    (net (code "131") (name "/FX3_CTL7") (class "Default")
      (node (ref "IC8") (pin "M7") (pinfunction "IO,_DIFFIO_L41n_M7") (pintype "bidirectional"))
    )
    (net (code "132") (name "/FX3_CTL8") (class "Default")
      (node (ref "IC8") (pin "M8") (pinfunction "IO,_DIFFIO_L42p_M8") (pintype "bidirectional"))
    )
    (net (code "133") (name "/FX3_CTL9") (class "Default")
      (node (ref "IC8") (pin "N1") (pinfunction "IO,_DIFFIO_L29n,_(DQ1L)/(DQ3L)/(DQ1L)_N1") (pintype "bidirectional"))
    )
    (net (code "134") (name "/FX3_CTL10") (class "Default")
      (node (ref "IC8") (pin "N2") (pinfunction "IO,_DIFFIO_L29p,_(DQ1L)/(DQ3L)/(DQ1L)_N2") (pintype "bidirectional"))
    )
    (net (code "135") (name "/FX3_CTL11") (class "Default")
      (node (ref "IC8") (pin "N5") (pinfunction "IO,_(DQ1L)/(DQ3L)/(DQ1L)_N5") (pintype "bidirectional"))
    )
    (net (code "136") (name "/FX3_CTL12") (class "Default")
      (node (ref "IC8") (pin "N6") (pinfunction "IO,_DIFFIO_L41p,_(DQ3L)/(DQ3L)/(DQ1L)_N6") (pintype "bidirectional"))
    )
    (net (code "137") (name "/FX3_DCTL9") (class "Default")
      (node (ref "IC8") (pin "P2") (pinfunction "IO,_DIFFIO_L32p,_(DQ1L)/(DQ3L)/(DQ1L)_P2") (pintype "bidirectional"))
    )
    (net (code "138") (name "/FX3_DCTL10") (class "Default")
      (node (ref "IC8") (pin "N7") (pinfunction "IO,_DIFFIO_L49p_N7") (pintype "bidirectional"))
    )
    (net (code "139") (name "/FX3_LED_G") (class "Default")
      (node (ref "IC8") (pin "G5") (pinfunction "IO,_VREFB1N0_G5") (pintype "bidirectional"))
    )
    (net (code "140") (name "/FX3_LED_R") (class "Default")
      (node (ref "IC8") (pin "H5") (pinfunction "IO,_VREFB1N2_H5") (pintype "bidirectional"))
    )
    (net (code "141") (name "/LM75_OS") (class "Default")
      (node (ref "IC8") (pin "J6") (pinfunction "IO,_DIFFIO_L9n,_(DQ2L)/(DQ1L)/(DQ1L)_J6") (pintype "bidirectional"))
    )
    (net (code "142") (name "GND") (class "Default")
      (node (ref "C103") (pin "2") (pinfunction "2_2") (pintype "passive"))
      (node (ref "C104") (pin "2") (pinfunction "2_2") (pintype "passive"))
      (node (ref "C105") (pin "2") (pinfunction "2_2") (pintype "passive"))
      (node (ref "C106") (pin "2") (pinfunction "2_2") (pintype "passive"))
      (node (ref "C107") (pin "2") (pinfunction "2_2") (pintype "passive"))
      (node (ref "C108") (pin "2") (pinfunction "2_2") (pintype "passive"))
      (node (ref "C109") (pin "2") (pinfunction "2_2") (pintype "passive"))
      (node (ref "C110") (pin "2") (pinfunction "2_2") (pintype "passive"))
      (node (ref "C111") (pin "2") (pinfunction "2_2") (pintype "passive"))
      (node (ref "C112") (pin "2") (pinfunction "2_2") (pintype "passive"))
      (node (ref "C113") (pin "2") (pinfunction "2_2") (pintype "passive"))
      (node (ref "C114") (pin "2") (pinfunction "2_2") (pintype "passive"))
      (node (ref "R42") (pin "2") (pinfunction "2_2") (pintype "passive"))
      (node (ref "R43") (pin "2") (pinfunction "2_2") (pintype "passive"))
      (node (ref "R44") (pin "2") (pinfunction "2_2") (pintype "passive"))
      (node (ref "R45") (pin "2") (pinfunction "2_2") (pintype "passive"))
      (node (ref "R47") (pin "1") (pinfunction "1_1") (pintype "passive"))
    )
    (net (code "143") (name "Net-(IC8D-IO,_RDN2)") (class "Default")
      (node (ref "IC8") (pin "AB19") (pinfunction "IO,_RDN2_AB19") (pintype "bidirectional"))
      (node (ref "R47") (pin "2") (pinfunction "2_2") (pintype "passive"))
    )
    (net (code "144") (name "Net-(IC8D-IO,_RUP2)") (class "Default")
      (node (ref "IC8") (pin "AA19") (pinfunction "IO,_RUP2_AA19") (pintype "bidirectional"))
      (node (ref "R46") (pin "1") (pinfunction "1_1") (pintype "passive"))
    )
    (net (code "145") (name "VCC1P8") (class "Default")
      (node (ref "R46") (pin "2") (pinfunction "2_2") (pintype "passive"))
    )
    (net (code "146") (name "VREF_DDR2") (class "Default")
      (node (ref "C103") (pin "1") (pinfunction "1_1") (pintype "passive"))
      (node (ref "C104") (pin "1") (pinfunction "1_1") (pintype "passive"))
      (node (ref "C105") (pin "1") (pinfunction "1_1") (pintype "passive"))
      (node (ref "C106") (pin "1") (pinfunction "1_1") (pintype "passive"))
      (node (ref "C107") (pin "1") (pinfunction "1_1") (pintype "passive"))
      (node (ref "C108") (pin "1") (pinfunction "1_1") (pintype "passive"))
      (node (ref "C109") (pin "1") (pinfunction "1_1") (pintype "passive"))
      (node (ref "C110") (pin "1") (pinfunction "1_1") (pintype "passive"))
      (node (ref "C111") (pin "1") (pinfunction "1_1") (pintype "passive"))
      (node (ref "C112") (pin "1") (pinfunction "1_1") (pintype "passive"))
      (node (ref "C113") (pin "1") (pinfunction "1_1") (pintype "passive"))
      (node (ref "C114") (pin "1") (pinfunction "1_1") (pintype "passive"))
      (node (ref "IC8") (pin "AA18") (pinfunction "IO,_VREFB4N1_AA18") (pintype "bidirectional"))
      (node (ref "IC8") (pin "AB4") (pinfunction "IO,_VREFB3N2_AB4") (pintype "bidirectional"))
      (node (ref "IC8") (pin "M5") (pinfunction "IO,_VREFB2N0_M5") (pintype "bidirectional"))
      (node (ref "IC8") (pin "P5") (pinfunction "IO,_VREFB2N1_P5") (pintype "bidirectional"))
      (node (ref "IC8") (pin "R5") (pinfunction "IO,_VREFB2N3_R5") (pintype "bidirectional"))
      (node (ref "IC8") (pin "T3") (pinfunction "IO,_VREFB2N2_T3") (pintype "bidirectional"))
      (node (ref "IC8") (pin "U11") (pinfunction "IO,_VREFB3N0_U11") (pintype "bidirectional"))
      (node (ref "IC8") (pin "V12") (pinfunction "IO,_VREFB4N3_V12") (pintype "bidirectional"))
      (node (ref "IC8") (pin "V16") (pinfunction "IO,_VREFB4N0_V16") (pintype "bidirectional"))
      (node (ref "IC8") (pin "V9") (pinfunction "IO,_VREFB3N1_V9") (pintype "bidirectional"))
      (node (ref "IC8") (pin "W14") (pinfunction "IO,_VREFB4N2_W14") (pintype "bidirectional"))
      (node (ref "IC8") (pin "Y4") (pinfunction "IO,_VREFB3N3_Y4") (pintype "bidirectional"))
    )
    (net (code "147") (name "unconnected-(IC8B-IO,_DIFFIO_L34n,_(DQ1L){slash}(DQ3L){slash}(DQ1L)-PadP3)") (class "Default")
      (node (ref "IC8") (pin "P3") (pinfunction "IO,_DIFFIO_L34n,_(DQ1L)/(DQ3L)/(DQ1L)_P3") (pintype "bidirectional+no_connect"))
    )
    (net (code "148") (name "unconnected-(IC8B-IO,_DIFFIO_L34p,_(DQS1L{slash}CQ1L#,DPCLK1){slash}(DQS1L{slash}CQ1L#,DPCLK1){slash}(DQS1L{slash}CQ1L#,DPCLK1)-PadP4)") (class "Default")
      (node (ref "IC8") (pin "P4") (pinfunction "IO,_DIFFIO_L34p,_(DQS1L/CQ1L#,DPCLK1)/(DQS1L/CQ1L#,DPCLK1)/(DQS1L/CQ1L#,DPCLK1)_P4") (pintype "bidirectional+no_connect"))
    )
  )
)
